# Intar_RGB_Module.net
KiCad netlist of a schematic drawn in EAGLE
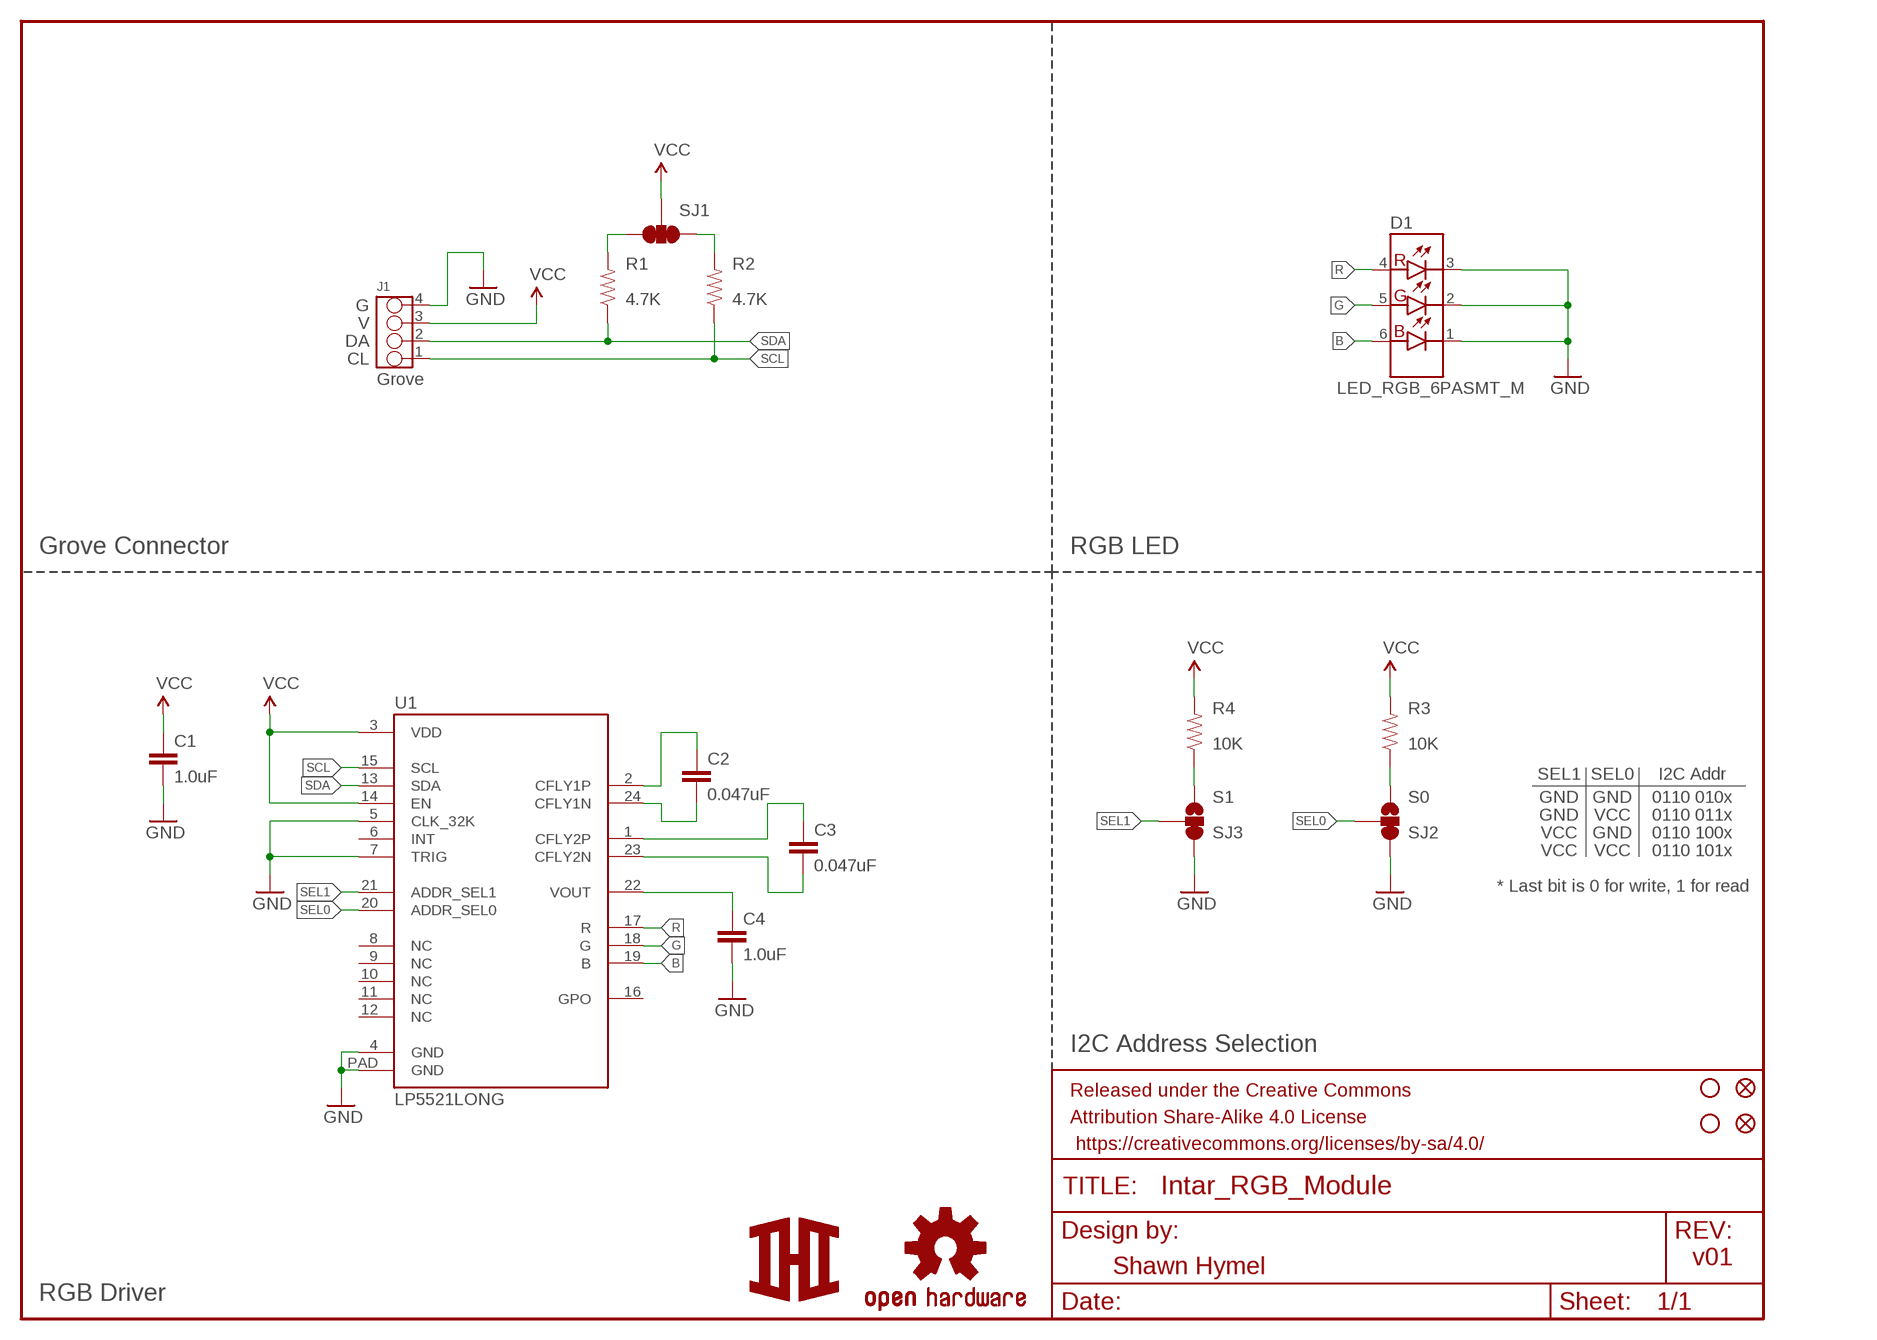
[diagram p0: schematic, sheet 1]

(export (version "E")
  (design (tool "Eeschema 10.0.6"))
  (components
    (comp (ref "C1")
      (value "1.0uF")
      (footprint "eagle-import:0603-CAP")
      (libsource (lib "eagle-import") (part "1.0UF-16V-10%(0603)"))
    )
    (comp (ref "C2")
      (value "0.047uF")
      (footprint "eagle-import:0603-CAP")
      (libsource (lib "eagle-import") (part "CAP0603-CAP"))
    )
    (comp (ref "C3")
      (value "0.047uF")
      (footprint "eagle-import:0603-CAP")
      (libsource (lib "eagle-import") (part "CAP0603-CAP"))
    )
    (comp (ref "C4")
      (value "1.0uF")
      (footprint "eagle-import:0603-CAP")
      (libsource (lib "eagle-import") (part "1.0UF-16V-10%(0603)"))
    )
    (comp (ref "D1")
      (value "LED_RGB_6PASMT_M")
      (footprint "eagle-import:ASMT-YTB7-0AA02_M")
      (libsource (lib "eagle-import") (part "LED_RGB_6PASMT_M"))
    )
    (comp (ref "FID1")
      (value "FIDUCIAL1X2")
      (footprint "eagle-import:FIDUCIAL-1X2")
      (libsource (lib "eagle-import") (part "FIDUCIAL1X2"))
    )
    (comp (ref "FID2")
      (value "FIDUCIAL1X2")
      (footprint "eagle-import:FIDUCIAL-1X2")
      (libsource (lib "eagle-import") (part "FIDUCIAL1X2"))
    )
    (comp (ref "FRAME1")
      (value "FRAME-LETTER")
      (footprint "eagle-import:CREATIVE_COMMONS")
      (libsource (lib "eagle-import") (part "FRAME-LETTER"))
    )
    (comp (ref "J1")
      (value "GROVE-4P-2.0-3470130P1")
      (footprint "eagle-import:4P-2.0")
      (libsource (lib "eagle-import") (part "GROVE-4P-2.0-3470130P1"))
    )
    (comp (ref "LOGO1")
      (value "OSHW-LOGOS")
      (footprint "eagle-import:OSHW-LOGO-S")
      (libsource (lib "eagle-import") (part "OSHW-LOGOS"))
    )
    (comp (ref "R1")
      (value "4.7K")
      (footprint "eagle-import:0603-RES")
      (libsource (lib "eagle-import") (part "4.7KOHM-1/10W-1%(0603)"))
    )
    (comp (ref "R2")
      (value "4.7K")
      (footprint "eagle-import:0603-RES")
      (libsource (lib "eagle-import") (part "4.7KOHM-1/10W-1%(0603)"))
    )
    (comp (ref "R3")
      (value "10K")
      (footprint "eagle-import:0603-RES")
      (libsource (lib "eagle-import") (part "10KOHM-1/10W-1%(0603)0603"))
    )
    (comp (ref "R4")
      (value "10K")
      (footprint "eagle-import:0603-RES")
      (libsource (lib "eagle-import") (part "10KOHM-1/10W-1%(0603)0603"))
    )
    (comp (ref "SJ1")
      (value "SOLDERJUMPER_2WAYPASTE1&2&3")
      (footprint "eagle-import:SJ_3_PASTE1&2&3")
      (libsource (lib "eagle-import") (part "SOLDERJUMPER_2WAYPASTE1&2&3"))
    )
    (comp (ref "SJ2")
      (value "SOLDERJUMPER_2WAYPASTE2&3")
      (footprint "eagle-import:SJ_3_PASTE2&3")
      (libsource (lib "eagle-import") (part "SOLDERJUMPER_2WAYPASTE2&3"))
    )
    (comp (ref "SJ3")
      (value "SOLDERJUMPER_2WAYPASTE2&3")
      (footprint "eagle-import:SJ_3_PASTE2&3")
      (libsource (lib "eagle-import") (part "SOLDERJUMPER_2WAYPASTE2&3"))
    )
    (comp (ref "STANDOFF1")
      (value "STAND-OFF")
      (footprint "eagle-import:STAND-OFF")
      (libsource (lib "eagle-import") (part "STAND-OFF"))
    )
    (comp (ref "STANDOFF2")
      (value "STAND-OFF")
      (footprint "eagle-import:STAND-OFF")
      (libsource (lib "eagle-import") (part "STAND-OFF"))
    )
    (comp (ref "U$1")
      (value "LOGOSM")
      (footprint "eagle-import:LOGO_SM")
      (libsource (lib "eagle-import") (part "LOGOSM"))
    )
    (comp (ref "U1")
      (value "LP5521LONG")
      (footprint "eagle-import:WQFN-24_LONG")
      (libsource (lib "eagle-import") (part "LP5521LONG"))
    )
  )
  (nets
    (net (code "1") (name "B") (class "Default")
      (node (ref "D1") (pin "6") (pinfunction "B_A_6") (pintype "passive"))
      (node (ref "U1") (pin "19") (pinfunction "B_19") (pintype "bidirectional"))
    )
    (net (code "2") (name "G") (class "Default")
      (node (ref "D1") (pin "5") (pinfunction "G_A_5") (pintype "passive"))
      (node (ref "U1") (pin "18") (pinfunction "G_18") (pintype "bidirectional"))
    )
    (net (code "3") (name "GND") (class "Default")
      (node (ref "C1") (pin "2") (pinfunction "2_2") (pintype "passive"))
      (node (ref "C4") (pin "2") (pinfunction "2_2") (pintype "passive"))
      (node (ref "D1") (pin "1") (pinfunction "B_C_1") (pintype "passive"))
      (node (ref "D1") (pin "2") (pinfunction "G_C_2") (pintype "passive"))
      (node (ref "D1") (pin "3") (pinfunction "R_C_3") (pintype "passive"))
      (node (ref "J1") (pin "4") (pinfunction "4_4") (pintype "bidirectional"))
      (node (ref "SJ2") (pin "3") (pinfunction "3_3") (pintype "passive"))
      (node (ref "SJ3") (pin "3") (pinfunction "3_3") (pintype "passive"))
      (node (ref "U1") (pin "4") (pinfunction "GND_4") (pintype "bidirectional"))
      (node (ref "U1") (pin "5") (pinfunction "CLK_32K_5") (pintype "bidirectional"))
      (node (ref "U1") (pin "7") (pinfunction "TRIG_7") (pintype "bidirectional"))
      (node (ref "U1") (pin "PAD") (pinfunction "GND_PAD") (pintype "bidirectional"))
    )
    (net (code "4") (name "Net-(R1-Pad2)") (class "Default")
      (node (ref "R1") (pin "2") (pinfunction "2_2") (pintype "passive"))
      (node (ref "SJ1") (pin "3") (pinfunction "3_3") (pintype "passive"))
    )
    (net (code "5") (name "Net-(R2-Pad2)") (class "Default")
      (node (ref "R2") (pin "2") (pinfunction "2_2") (pintype "passive"))
      (node (ref "SJ1") (pin "1") (pinfunction "1_1") (pintype "passive"))
    )
    (net (code "6") (name "Net-(R3-Pad1)") (class "Default")
      (node (ref "R3") (pin "1") (pinfunction "1_1") (pintype "passive"))
      (node (ref "SJ2") (pin "1") (pinfunction "1_1") (pintype "passive"))
    )
    (net (code "7") (name "Net-(R4-Pad1)") (class "Default")
      (node (ref "R4") (pin "1") (pinfunction "1_1") (pintype "passive"))
      (node (ref "SJ3") (pin "1") (pinfunction "1_1") (pintype "passive"))
    )
    (net (code "8") (name "Net-(U1-CFLY1N)") (class "Default")
      (node (ref "C2") (pin "2") (pinfunction "2_2") (pintype "passive"))
      (node (ref "U1") (pin "24") (pinfunction "CFLY1N_24") (pintype "bidirectional"))
    )
    (net (code "9") (name "Net-(U1-CFLY1P)") (class "Default")
      (node (ref "C2") (pin "1") (pinfunction "1_1") (pintype "passive"))
      (node (ref "U1") (pin "2") (pinfunction "CFLY1P_2") (pintype "bidirectional"))
    )
    (net (code "10") (name "Net-(U1-CFLY2N)") (class "Default")
      (node (ref "C3") (pin "2") (pinfunction "2_2") (pintype "passive"))
      (node (ref "U1") (pin "23") (pinfunction "CFLY2N_23") (pintype "bidirectional"))
    )
    (net (code "11") (name "Net-(U1-CFLY2P)") (class "Default")
      (node (ref "C3") (pin "1") (pinfunction "1_1") (pintype "passive"))
      (node (ref "U1") (pin "1") (pinfunction "CFLY2P_1") (pintype "bidirectional"))
    )
    (net (code "12") (name "Net-(U1-VOUT)") (class "Default")
      (node (ref "C4") (pin "1") (pinfunction "1_1") (pintype "passive"))
      (node (ref "U1") (pin "22") (pinfunction "VOUT_22") (pintype "bidirectional"))
    )
    (net (code "13") (name "R") (class "Default")
      (node (ref "D1") (pin "4") (pinfunction "R_A_4") (pintype "passive"))
      (node (ref "U1") (pin "17") (pinfunction "R_17") (pintype "bidirectional"))
    )
    (net (code "14") (name "SCL") (class "Default")
      (node (ref "J1") (pin "1") (pinfunction "1_1") (pintype "bidirectional"))
      (node (ref "R2") (pin "1") (pinfunction "1_1") (pintype "passive"))
      (node (ref "U1") (pin "15") (pinfunction "SCL_15") (pintype "bidirectional"))
    )
    (net (code "15") (name "SDA") (class "Default")
      (node (ref "J1") (pin "2") (pinfunction "2_2") (pintype "bidirectional"))
      (node (ref "R1") (pin "1") (pinfunction "1_1") (pintype "passive"))
      (node (ref "U1") (pin "13") (pinfunction "SDA_13") (pintype "bidirectional"))
    )
    (net (code "16") (name "SEL0") (class "Default")
      (node (ref "SJ2") (pin "2") (pinfunction "2_2") (pintype "passive"))
      (node (ref "U1") (pin "20") (pinfunction "ADDR_SEL0_20") (pintype "bidirectional"))
    )
    (net (code "17") (name "SEL1") (class "Default")
      (node (ref "SJ3") (pin "2") (pinfunction "2_2") (pintype "passive"))
      (node (ref "U1") (pin "21") (pinfunction "ADDR_SEL1_21") (pintype "bidirectional"))
    )
    (net (code "18") (name "VCC") (class "Default")
      (node (ref "C1") (pin "1") (pinfunction "1_1") (pintype "passive"))
      (node (ref "J1") (pin "3") (pinfunction "3_3") (pintype "bidirectional"))
      (node (ref "R3") (pin "2") (pinfunction "2_2") (pintype "passive"))
      (node (ref "R4") (pin "2") (pinfunction "2_2") (pintype "passive"))
      (node (ref "SJ1") (pin "2") (pinfunction "2_2") (pintype "passive"))
      (node (ref "U1") (pin "14") (pinfunction "EN_14") (pintype "bidirectional"))
      (node (ref "U1") (pin "3") (pinfunction "VDD_3") (pintype "bidirectional"))
    )
    (net (code "19") (name "unconnected-(U1-GPO-Pad16)") (class "Default")
      (node (ref "U1") (pin "16") (pinfunction "GPO_16") (pintype "bidirectional"))
    )
    (net (code "20") (name "unconnected-(U1-INT-Pad6)") (class "Default")
      (node (ref "U1") (pin "6") (pinfunction "INT_6") (pintype "bidirectional"))
    )
    (net (code "21") (name "unconnected-(U1-NC-Pad8)") (class "Default")
      (node (ref "U1") (pin "8") (pinfunction "NC_8") (pintype "bidirectional"))
    )
    (net (code "22") (name "unconnected-(U1-NC-Pad9)") (class "Default")
      (node (ref "U1") (pin "9") (pinfunction "NC_9") (pintype "bidirectional"))
    )
    (net (code "23") (name "unconnected-(U1-NC-Pad10)") (class "Default")
      (node (ref "U1") (pin "10") (pinfunction "NC_10") (pintype "bidirectional"))
    )
    (net (code "24") (name "unconnected-(U1-NC-Pad11)") (class "Default")
      (node (ref "U1") (pin "11") (pinfunction "NC_11") (pintype "bidirectional"))
    )
    (net (code "25") (name "unconnected-(U1-NC-Pad12)") (class "Default")
      (node (ref "U1") (pin "12") (pinfunction "NC_12") (pintype "bidirectional"))
    )
  )
)
